# RS485_Communication_Layer.net
KiCad netlist of a schematic drawn in Altium Designer
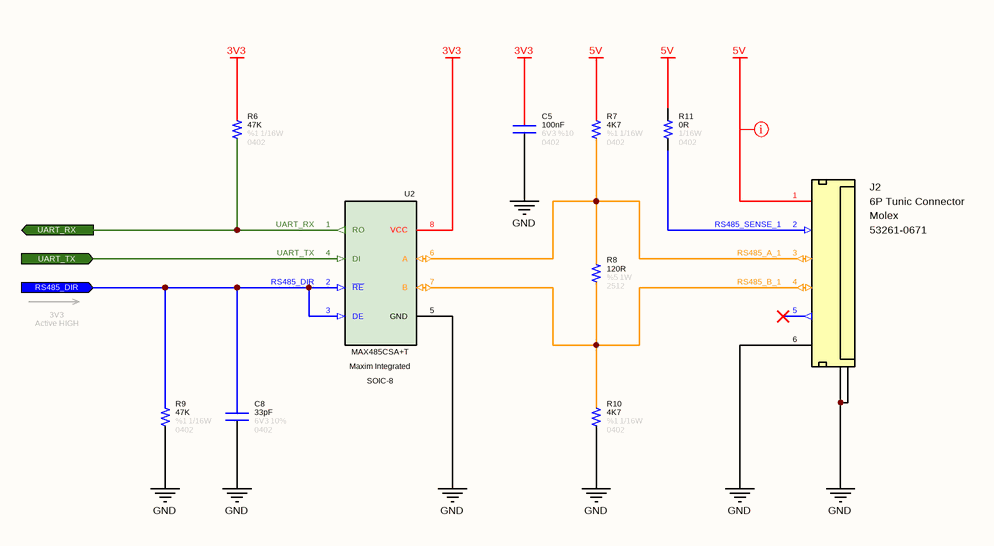
[diagram p0: RS485 Communication Layer.SchDoc]

(export (version "E")
  (design (tool "Eeschema 10.0.6"))
  (components
    (comp (ref "C5")
      (value "100nF")
      (footprint "CAPACITOR_0402")
      (description "Capacitor - 100nF [0402-6V3] (Ceramic)")
      (fields
        (field (name "MANUFACTURER PART NUMBER") "04026D104KAT4A")
        (field (name "TOLERANCE") "%10")
        (field (name "VOLTAGE") "6V3")
        (field (name "CASE") "0402")
        (field (name "Comment") "Capacitor - 100nF [0402] (Ceramic)")
      )
      (libsource (lib "Akkoyun") (part "Capacitor - 100nF [0402-6V3]"))
    )
    (comp (ref "C8")
      (value "33pF")
      (footprint "CAPACITOR_0402")
      (description "Capacitor - 33pF [0402] (Ceramic)")
      (fields
        (field (name "MANUFACTURER PART NUMBER") "C0402C330J9RACAUTO")
        (field (name "TOLERANCE") "10%")
        (field (name "CASE") "0402")
        (field (name "VOLTAGE") "6V3")
      )
      (libsource (lib "Akkoyun") (part "Capacitor - 33pF [0402-6V3]"))
    )
    (comp (ref "J2")
      (value "6P Tunic Connector")
      (footprint "Connector_Tunic 6P")
      (description "Mini Tunic Connector with 6P")
      (fields
        (field (name "MANUFACTURER PART NUMBER") "53261-0671")
        (field (name "MANUFACTURER NAME") "Molex")
      )
      (libsource (lib "Akkoyun") (part "Connector - Mini Tunic 6P (1.25)"))
    )
    (comp (ref "R6")
      (value "47K")
      (footprint "RESISTOR_0402")
      (description "Thick Film Resistors - SMD 1/16 W 47 KOhm 1%")
      (fields
        (field (name "MANUFACTURER PART NUMBER") "CRCW040247K0FKED")
        (field (name "TOLERANCE") "%1")
        (field (name "CASE") "0402")
        (field (name "POWER") "1/16W")
        (field (name "Comment") "47K - 0402 - %1 - 1/16W")
      )
      (libsource (lib "Akkoyun") (part "Resistor - 47K [0402]"))
    )
    (comp (ref "R7")
      (value "4K7")
      (footprint "RESISTOR_0402")
      (description "Thick Film Resistors - SMD 1/16 W 4.7 KOhm 1%")
      (fields
        (field (name "MANUFACTURER PART NUMBER") "CRCW04024K70FKED")
        (field (name "TOLERANCE") "%1")
        (field (name "CASE") "0402")
        (field (name "POWER") "1/16W")
        (field (name "Comment") "4K7 - 0402 - %1 - 1/16W")
      )
      (libsource (lib "Akkoyun") (part "Resistor - 4K7 [0402]"))
    )
    (comp (ref "R8")
      (value "120R")
      (footprint "RESISTOR_2512")
      (description "Thick Film Resistors - SMD 1 W 120 Ohm 5%")
      (fields
        (field (name "MANUFACTURER PART NUMBER") "RC2512JK-07120RL")
        (field (name "TOLERANCE") "%5")
        (field (name "CASE") "2512")
        (field (name "POWER") "1W")
        (field (name "Comment") "120R - 2512 - %5 - 1W")
      )
      (libsource (lib "Akkoyun") (part "Resistor - 120R [2512]"))
    )
    (comp (ref "R9")
      (value "47K")
      (footprint "RESISTOR_0402")
      (description "Thick Film Resistors - SMD 1/16 W 47 KOhm 1%")
      (fields
        (field (name "MANUFACTURER PART NUMBER") "CRCW040247K0FKED")
        (field (name "TOLERANCE") "%1")
        (field (name "CASE") "0402")
        (field (name "POWER") "1/16W")
        (field (name "Comment") "47K - 0402 - %1 - 1/16W")
      )
      (libsource (lib "Akkoyun") (part "Resistor - 47K [0402]"))
    )
    (comp (ref "R10")
      (value "4K7")
      (footprint "RESISTOR_0402")
      (description "Thick Film Resistors - SMD 1/16 W 4.7 KOhm 1%")
      (fields
        (field (name "MANUFACTURER PART NUMBER") "CRCW04024K70FKED")
        (field (name "TOLERANCE") "%1")
        (field (name "CASE") "0402")
        (field (name "POWER") "1/16W")
        (field (name "Comment") "4K7 - 0402 - %1 - 1/16W")
      )
      (libsource (lib "Akkoyun") (part "Resistor - 4K7 [0402]"))
    )
    (comp (ref "R11")
      (value "0R")
      (footprint "RESISTOR_0402")
      (description "Thick Film Resistors - SMD 1/16 W 0 Ohm")
      (fields
        (field (name "MANUFACTURER PART NUMBER") "CRCW04020000Z0ED")
        (field (name "CASE") "0402")
        (field (name "POWER") "1/16W")
        (field (name "Comment") "0R - 0402 - %1 - 1/16W")
      )
      (libsource (lib "Akkoyun") (part "Resistor - 0R [0402]"))
    )
    (comp (ref "U2")
      (value "RS485 Modulator")
      (footprint "SOP-8L (AZRS3080E)")
      (description "RS-422/RS-485 Interface IC Low-Power, Slew-Rate-Limited RS-485/RS-422 Transceivers")
      (fields
        (field (name "CASE") "SOIC-8")
        (field (name "MANUFACTURER PART NUMBER") "MAX485CSA+T")
        (field (name "MANUFACTURER NAME") "Maxim Integrated")
      )
      (libsource (lib "Akkoyun") (part "IC - MAX485CSA+T"))
    )
  )
  (nets
    (net (code "1") (name "/RS485_A_1") (class "Default")
      (node (ref "J2") (pin "3") (pinfunction "RS485-A_3") (pintype "bidirectional"))
      (node (ref "R7") (pin "1") (pinfunction "1_1") (pintype "passive"))
      (node (ref "R8") (pin "2") (pinfunction "2_2") (pintype "passive"))
      (node (ref "U2") (pin "6") (pinfunction "A_6") (pintype "bidirectional"))
    )
    (net (code "2") (name "/RS485_B_1") (class "Default")
      (node (ref "J2") (pin "4") (pinfunction "RS485-B_4") (pintype "bidirectional"))
      (node (ref "R10") (pin "2") (pinfunction "2_2") (pintype "passive"))
      (node (ref "R8") (pin "1") (pinfunction "1_1") (pintype "passive"))
      (node (ref "U2") (pin "7") (pinfunction "B_7") (pintype "bidirectional"))
    )
    (net (code "3") (name "/RS485_DIR") (class "Default")
      (node (ref "C8") (pin "2") (pinfunction "2_2") (pintype "passive"))
      (node (ref "R9") (pin "2") (pinfunction "2_2") (pintype "passive"))
      (node (ref "U2") (pin "2") (pinfunction "~{RE}_2") (pintype "input"))
      (node (ref "U2") (pin "3") (pinfunction "DE_3") (pintype "input"))
    )
    (net (code "4") (name "/RS485_SENSE_1") (class "Default")
      (node (ref "J2") (pin "2") (pinfunction "Sense_2") (pintype "input"))
      (node (ref "R11") (pin "1") (pinfunction "1_1") (pintype "passive"))
    )
    (net (code "5") (name "/UART_RX") (class "Default")
      (node (ref "R6") (pin "1") (pinfunction "1_1") (pintype "passive"))
      (node (ref "U2") (pin "1") (pinfunction "RO_1") (pintype "output"))
    )
    (net (code "6") (name "/UART_TX") (class "Default")
      (node (ref "U2") (pin "4") (pinfunction "DI_4") (pintype "input"))
    )
    (net (code "7") (name "3V3") (class "Default")
      (node (ref "C5") (pin "2") (pinfunction "2_2") (pintype "passive"))
      (node (ref "R6") (pin "2") (pinfunction "2_2") (pintype "passive"))
      (node (ref "U2") (pin "8") (pinfunction "VCC_8") (pintype "power_in"))
    )
    (net (code "8") (name "5V") (class "Default")
      (node (ref "J2") (pin "1") (pinfunction "5V_1") (pintype "power_in"))
      (node (ref "R11") (pin "2") (pinfunction "2_2") (pintype "passive"))
      (node (ref "R7") (pin "2") (pinfunction "2_2") (pintype "passive"))
    )
    (net (code "9") (name "GND") (class "Default")
      (node (ref "C5") (pin "1") (pinfunction "1_1") (pintype "passive"))
      (node (ref "C8") (pin "1") (pinfunction "1_1") (pintype "passive"))
      (node (ref "J2") (pin "6") (pinfunction "GND_6") (pintype "power_in"))
      (node (ref "J2") (pin "7") (pinfunction "GND_7") (pintype "passive"))
      (node (ref "J2") (pin "8") (pinfunction "GND_8") (pintype "passive"))
      (node (ref "R10") (pin "1") (pinfunction "1_1") (pintype "passive"))
      (node (ref "R9") (pin "1") (pinfunction "1_1") (pintype "passive"))
      (node (ref "U2") (pin "5") (pinfunction "GND_5") (pintype "passive"))
    )
    (net (code "10") (name "unconnected-(J2-INT-Pad5)") (class "Default")
      (node (ref "J2") (pin "5") (pinfunction "INT_5") (pintype "output+no_connect"))
    )
  )
)
